# relay_distribution_brd.net
KiCad netlist of a schematic drawn in EAGLE
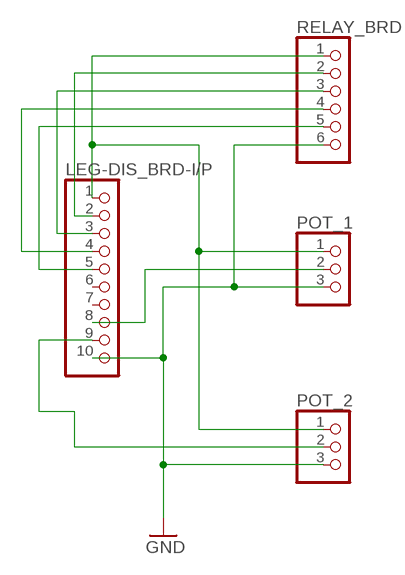
[diagram p0: schematic, sheet 1]

(export (version "E")
  (design (tool "Eeschema 10.0.6"))
  (components
    (comp (ref "LEG-DIS_BRD-I/P")
      (value "PINHD-1X10")
      (footprint "eagle-import:1X10")
      (libsource (lib "eagle-import") (part "PINHD-1X10"))
    )
    (comp (ref "POT_1")
      (value "PINHD-1X3")
      (footprint "eagle-import:1X03")
      (libsource (lib "eagle-import") (part "PINHD-1X3"))
    )
    (comp (ref "POT_2")
      (value "PINHD-1X3")
      (footprint "eagle-import:1X03")
      (libsource (lib "eagle-import") (part "PINHD-1X3"))
    )
    (comp (ref "RELAY_BRD")
      (value "PINHD-1X6")
      (footprint "eagle-import:1X06")
      (libsource (lib "eagle-import") (part "PINHD-1X6"))
    )
  )
  (nets
    (net (code "1") (name "GND") (class "Default")
      (node (ref "LEG-DIS_BRD-I/P") (pin "10") (pinfunction "10_10") (pintype "passive"))
      (node (ref "POT_1") (pin "3") (pinfunction "3_3") (pintype "passive"))
      (node (ref "POT_2") (pin "3") (pinfunction "3_3") (pintype "passive"))
      (node (ref "RELAY_BRD") (pin "6") (pinfunction "6_6") (pintype "passive"))
    )
    (net (code "2") (name "Net-(LEG-DIS_BRD-I/P-Pad1)") (class "Default")
      (node (ref "LEG-DIS_BRD-I/P") (pin "1") (pinfunction "1_1") (pintype "passive"))
      (node (ref "POT_1") (pin "1") (pinfunction "1_1") (pintype "passive"))
      (node (ref "POT_2") (pin "1") (pinfunction "1_1") (pintype "passive"))
      (node (ref "RELAY_BRD") (pin "1") (pinfunction "1_1") (pintype "passive"))
    )
    (net (code "3") (name "Net-(LEG-DIS_BRD-I/P-Pad2)") (class "Default")
      (node (ref "LEG-DIS_BRD-I/P") (pin "2") (pinfunction "2_2") (pintype "passive"))
      (node (ref "RELAY_BRD") (pin "2") (pinfunction "2_2") (pintype "passive"))
    )
    (net (code "4") (name "Net-(LEG-DIS_BRD-I/P-Pad3)") (class "Default")
      (node (ref "LEG-DIS_BRD-I/P") (pin "3") (pinfunction "3_3") (pintype "passive"))
      (node (ref "RELAY_BRD") (pin "3") (pinfunction "3_3") (pintype "passive"))
    )
    (net (code "5") (name "Net-(LEG-DIS_BRD-I/P-Pad4)") (class "Default")
      (node (ref "LEG-DIS_BRD-I/P") (pin "4") (pinfunction "4_4") (pintype "passive"))
      (node (ref "RELAY_BRD") (pin "4") (pinfunction "4_4") (pintype "passive"))
    )
    (net (code "6") (name "Net-(LEG-DIS_BRD-I/P-Pad5)") (class "Default")
      (node (ref "LEG-DIS_BRD-I/P") (pin "5") (pinfunction "5_5") (pintype "passive"))
      (node (ref "RELAY_BRD") (pin "5") (pinfunction "5_5") (pintype "passive"))
    )
    (net (code "7") (name "Net-(LEG-DIS_BRD-I/P-Pad8)") (class "Default")
      (node (ref "LEG-DIS_BRD-I/P") (pin "8") (pinfunction "8_8") (pintype "passive"))
      (node (ref "POT_1") (pin "2") (pinfunction "2_2") (pintype "passive"))
    )
    (net (code "8") (name "Net-(LEG-DIS_BRD-I/P-Pad9)") (class "Default")
      (node (ref "LEG-DIS_BRD-I/P") (pin "9") (pinfunction "9_9") (pintype "passive"))
      (node (ref "POT_2") (pin "2") (pinfunction "2_2") (pintype "passive"))
    )
    (net (code "9") (name "unconnected-(LEG-DIS_BRD-I/P-Pad6)") (class "Default")
      (node (ref "LEG-DIS_BRD-I/P") (pin "6") (pinfunction "6_6") (pintype "passive"))
    )
    (net (code "10") (name "unconnected-(LEG-DIS_BRD-I/P-Pad7)") (class "Default")
      (node (ref "LEG-DIS_BRD-I/P") (pin "7") (pinfunction "7_7") (pintype "passive"))
    )
  )
)
